# CH32V006K8U-R0.net
KiCad netlist of a schematic drawn in Altium Designer
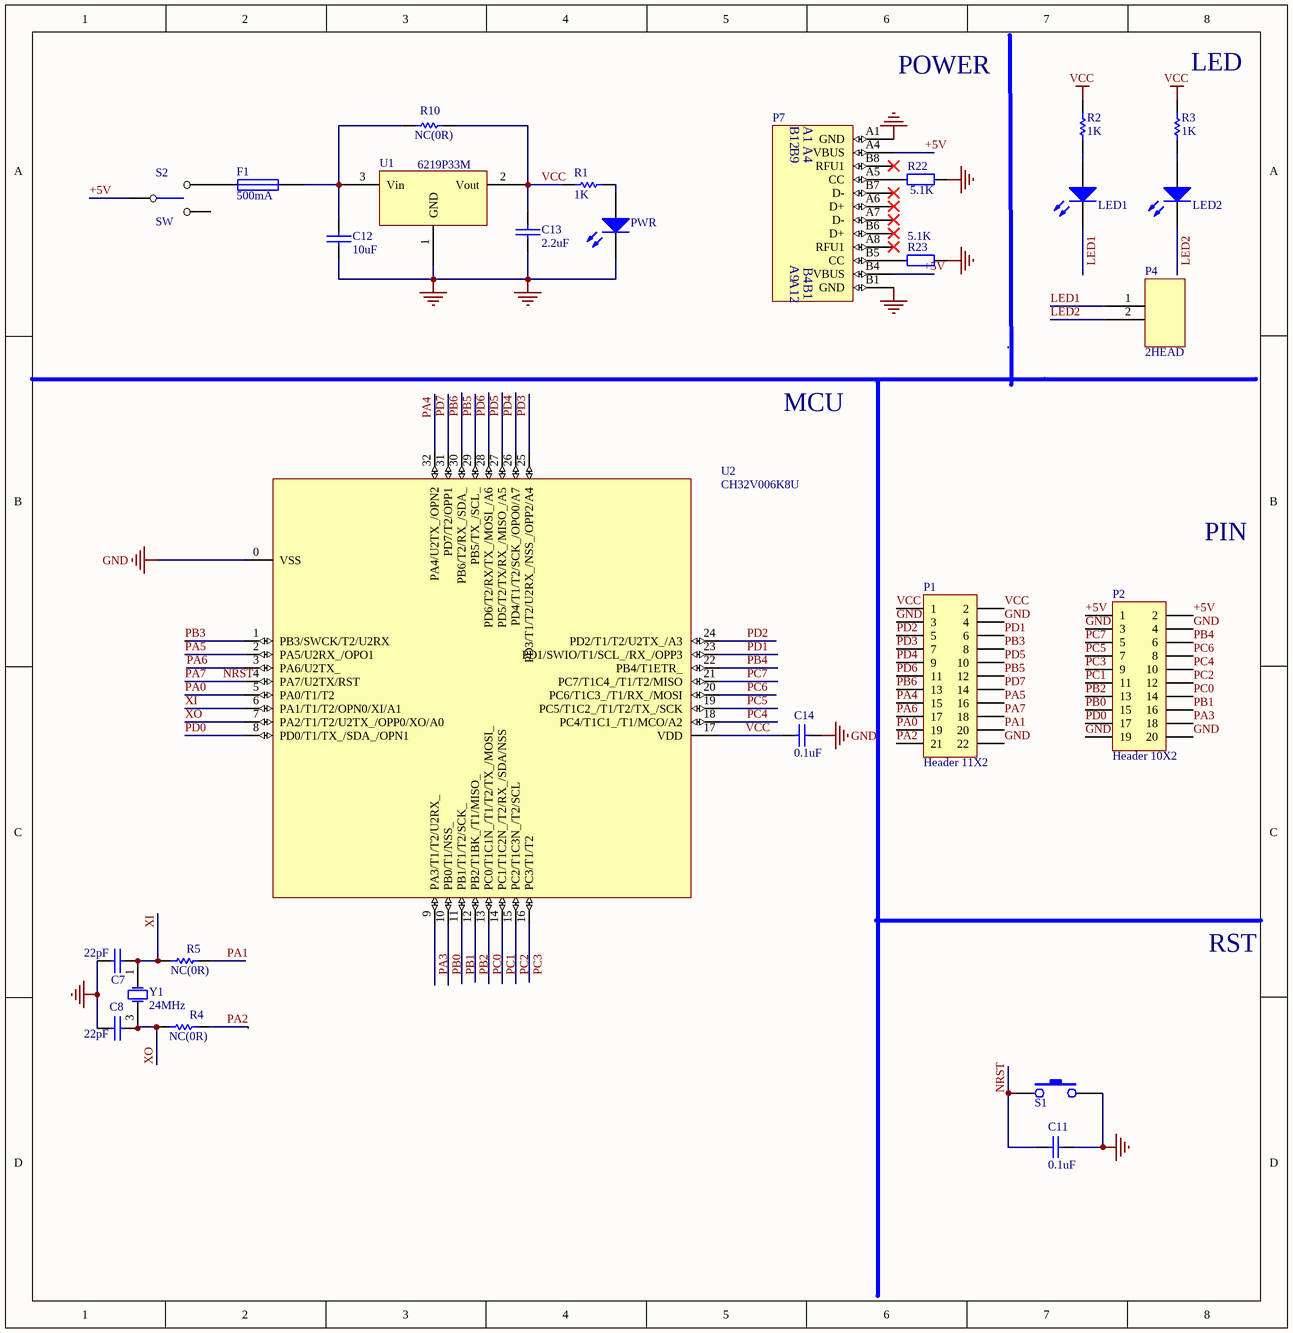
[diagram p0: CH32V006K8U-R0.SchDoc]

(export (version "E")
  (design (tool "Eeschema 10.0.6"))
  (components
    (comp (ref "C7")
      (value "22pF")
      (footprint "0402_C")
      (description "Capacitor")
      (libsource (lib "*") (part "CAP"))
    )
    (comp (ref "C8")
      (value "22pF")
      (footprint "0402_C")
      (description "Capacitor")
      (libsource (lib "*") (part "CAP"))
    )
    (comp (ref "C11")
      (value "0.1uF")
      (footprint "0402_C")
      (description "Capacitor")
      (fields (field (name "PUBLISHER") "Altium Limited"))
      (libsource (lib "*") (part "Cap"))
    )
    (comp (ref "C12")
      (value "10uF")
      (footprint "0603_C")
      (description "Capacitor")
      (libsource (lib "wch_sch_others") (part "CAP"))
    )
    (comp (ref "C13")
      (value "2.2uF")
      (footprint "0402_C")
      (description "Capacitor")
      (libsource (lib "wch_sch_others") (part "CAP"))
    )
    (comp (ref "C14")
      (value "0.1uF")
      (footprint "0402_C")
      (description "Capacitor")
      (fields (field (name "PUBLISHER") "Altium Limited"))
      (libsource (lib "*") (part "Cap"))
    )
    (comp (ref "F1")
      (value "500mA")
      (footprint "0603")
      (description "Fuse")
      (libsource (lib "*") (part "FUSE1"))
    )
    (comp (ref "LED1")
      (value "LED1   blue")
      (footprint "0603+")
      (description "Typical INFRARED GaAs LED")
      (fields (field (name "PUBLISHER") "Altium Limited"))
      (libsource (lib "*") (part "LED0"))
    )
    (comp (ref "LED2")
      (value "LED2  blue")
      (footprint "0603+")
      (description "Typical INFRARED GaAs LED")
      (fields (field (name "PUBLISHER") "Altium Limited"))
      (libsource (lib "*") (part "LED0"))
    )
    (comp (ref "P1")
      (value "Header 11X2")
      (footprint "IDC22-2.54mm")
      (description "Header, 11-Pin, Dual row")
      (fields (field (name "PUBLISHER") "Altium Limited"))
      (libsource (lib "Miscellaneous Connectors") (part "Header 11X2"))
    )
    (comp (ref "P2")
      (value "Header 10X2")
      (footprint "IDC20-2.54mm")
      (description "Header, 10-Pin, Dual row")
      (fields (field (name "PUBLISHER") "Altium Limited"))
      (libsource (lib "Miscellaneous Connectors") (part "Header 10X2"))
    )
    (comp (ref "P4") (value "2HEAD") (footprint "SIP2-2.54mm") (libsource (lib "*") (part "2HEAD")))
    (comp (ref "P7")
      (value "TYPE-C")
      (footprint "TYPE-C-Receptacle-2.0")
      (libsource (lib "*") (part "TYPE-C1"))
    )
    (comp (ref "PWR")
      (value "POWER  red")
      (footprint "0603+")
      (description "Typical INFRARED GaAs LED")
      (fields (field (name "PUBLISHER") "Altium Limited"))
      (libsource (lib "") (part "LED0_1"))
    )
    (comp (ref "R1")
      (value "1K")
      (footprint "0402")
      (description "Semiconductor Resistor")
      (fields (field (name "PUBLISHER") "Altium Limited"))
      (libsource (lib "*") (part "Res Semi"))
    )
    (comp (ref "R2")
      (value "1K")
      (footprint "0402")
      (description "Semiconductor Resistor")
      (fields (field (name "PUBLISHER") "Altium Limited"))
      (libsource (lib "*") (part "Res Semi"))
    )
    (comp (ref "R3")
      (value "1K")
      (footprint "0402")
      (description "Semiconductor Resistor")
      (fields (field (name "PUBLISHER") "Altium Limited"))
      (libsource (lib "*") (part "Res Semi"))
    )
    (comp (ref "R4")
      (value "NC(0R)")
      (footprint "0402")
      (description "Semiconductor Resistor")
      (fields (field (name "Comment") "0R") (field (name "PUBLISHER") "Altium Limited"))
      (libsource (lib "*") (part "Res Semi"))
    )
    (comp (ref "R5")
      (value "NC(0R)")
      (footprint "0402")
      (description "Semiconductor Resistor")
      (fields (field (name "Comment") "0R") (field (name "PUBLISHER") "Altium Limited"))
      (libsource (lib "*") (part "Res Semi"))
    )
    (comp (ref "R10")
      (value "NC(0R)")
      (footprint "0402")
      (description "Semiconductor Resistor")
      (fields (field (name "Comment") "0R") (field (name "PUBLISHER") "Altium Limited"))
      (libsource (lib "*") (part "Res Semi"))
    )
    (comp (ref "R22")
      (value "5.1K")
      (footprint "0402")
      (description "Resistor")
      (libsource (lib "Miscellaneous Devices") (part "Res2"))
    )
    (comp (ref "R23")
      (value "5.1K")
      (footprint "0402")
      (description "Resistor")
      (libsource (lib "Miscellaneous Devices") (part "Res2"))
    )
    (comp (ref "S1") (value "NRST") (footprint "SMD_6.1x3.65x2.5mm-KEY") (libsource (lib "*") (part "KEY")))
    (comp (ref "S2") (value "SW") (footprint "SW1") (libsource (lib "*") (part "SW")))
    (comp (ref "U1")
      (value "6219P33M")
      (footprint "SOT-23")
      (libsource (lib "wch_sch_others") (part "6219P33M"))
    )
    (comp (ref "U2")
      (value "CH32V006K8U")
      (footprint "QFN32_4X4")
      (description "RISC-V MCU, 48MHz, ADC/OPA/2*UART/I2C/SPI")
      (libsource (lib "PCB_Project") (part "CH32V006K8U"))
    )
    (comp (ref "Y1")
      (value "24MHz")
      (footprint "XT3225")
      (description "Crystal Oscillator")
      (fields (field (name "PUBLISHER") "Altium Limited"))
      (libsource (lib "*") (part "XTAL"))
    )
  )
  (nets
    (net (code "1") (name "/+5V") (class "Default")
      (node (ref "P2") (pin "1") (pinfunction "1_1") (pintype "passive"))
      (node (ref "P2") (pin "2") (pinfunction "2_2") (pintype "passive"))
      (node (ref "P7") (pin "A4") (pinfunction "VBUS_A4") (pintype "bidirectional"))
      (node (ref "P7") (pin "B4") (pinfunction "VBUS_B4") (pintype "bidirectional"))
      (node (ref "S2") (pin "1") (pinfunction "1_1") (pintype "passive"))
    )
    (net (code "2") (name "/LED1") (class "Default")
      (node (ref "LED1") (pin "2") (pinfunction "K_2") (pintype "passive"))
      (node (ref "P4") (pin "1") (pintype "passive"))
    )
    (net (code "3") (name "/LED2") (class "Default")
      (node (ref "LED2") (pin "2") (pinfunction "K_2") (pintype "passive"))
      (node (ref "P4") (pin "2") (pintype "passive"))
    )
    (net (code "4") (name "/NRST") (class "Default")
      (node (ref "C11") (pin "2") (pinfunction "2_2") (pintype "passive"))
      (node (ref "P1") (pin "18") (pinfunction "18_18") (pintype "passive"))
      (node (ref "S1") (pin "1") (pinfunction "1_1") (pintype "passive"))
      (node (ref "U2") (pin "4") (pinfunction "PA7/U2TX/RST_4") (pintype "bidirectional"))
    )
    (net (code "5") (name "/PA0") (class "Default")
      (node (ref "P1") (pin "19") (pinfunction "19_19") (pintype "passive"))
      (node (ref "U2") (pin "5") (pinfunction "PA0/T1/T2_5") (pintype "bidirectional"))
    )
    (net (code "6") (name "/PA1") (class "Default")
      (node (ref "P1") (pin "20") (pinfunction "20_20") (pintype "passive"))
      (node (ref "R5") (pin "2") (pinfunction "2_2") (pintype "passive"))
    )
    (net (code "7") (name "/PA2") (class "Default")
      (node (ref "P1") (pin "21") (pinfunction "21_21") (pintype "passive"))
      (node (ref "R4") (pin "2") (pinfunction "2_2") (pintype "passive"))
    )
    (net (code "8") (name "/PA3") (class "Default")
      (node (ref "P2") (pin "18") (pinfunction "18_18") (pintype "passive"))
      (node (ref "U2") (pin "9") (pinfunction "PA3/T1/T2/U2RX__9") (pintype "bidirectional"))
    )
    (net (code "9") (name "/PA4") (class "Default")
      (node (ref "P1") (pin "15") (pinfunction "15_15") (pintype "passive"))
      (node (ref "U2") (pin "32") (pinfunction "PA4/U2TX_/OPN2_32") (pintype "bidirectional"))
    )
    (net (code "10") (name "/PA5") (class "Default")
      (node (ref "P1") (pin "16") (pinfunction "16_16") (pintype "passive"))
      (node (ref "U2") (pin "2") (pinfunction "PA5/U2RX_/OPO1_2") (pintype "bidirectional"))
    )
    (net (code "11") (name "/PA6") (class "Default")
      (node (ref "P1") (pin "17") (pinfunction "17_17") (pintype "passive"))
      (node (ref "U2") (pin "3") (pinfunction "PA6/U2TX__3") (pintype "bidirectional"))
    )
    (net (code "12") (name "/PB0") (class "Default")
      (node (ref "P2") (pin "15") (pinfunction "15_15") (pintype "passive"))
      (node (ref "U2") (pin "10") (pinfunction "PB0/T1/NSS__10") (pintype "bidirectional"))
    )
    (net (code "13") (name "/PB1") (class "Default")
      (node (ref "P2") (pin "16") (pinfunction "16_16") (pintype "passive"))
      (node (ref "U2") (pin "11") (pinfunction "PB1/T1/T2/SCK__11") (pintype "bidirectional"))
    )
    (net (code "14") (name "/PB2") (class "Default")
      (node (ref "P2") (pin "13") (pinfunction "13_13") (pintype "passive"))
      (node (ref "U2") (pin "12") (pinfunction "PB2/T1BK_/T1/MISO__12") (pintype "bidirectional"))
    )
    (net (code "15") (name "/PB3") (class "Default")
      (node (ref "P1") (pin "8") (pinfunction "8_8") (pintype "passive"))
      (node (ref "U2") (pin "1") (pinfunction "PB3/SWCK/T2/U2RX_1") (pintype "bidirectional"))
    )
    (net (code "16") (name "/PB4") (class "Default")
      (node (ref "P2") (pin "6") (pinfunction "6_6") (pintype "passive"))
      (node (ref "U2") (pin "22") (pinfunction "PB4/T1ETR__22") (pintype "bidirectional"))
    )
    (net (code "17") (name "/PB5") (class "Default")
      (node (ref "P1") (pin "12") (pinfunction "12_12") (pintype "passive"))
      (node (ref "U2") (pin "29") (pinfunction "PB5/TX_/SCL__29") (pintype "bidirectional"))
    )
    (net (code "18") (name "/PB6") (class "Default")
      (node (ref "P1") (pin "13") (pinfunction "13_13") (pintype "passive"))
      (node (ref "U2") (pin "30") (pinfunction "PB6/T2/RX_/SDA__30") (pintype "bidirectional"))
    )
    (net (code "19") (name "/PC0") (class "Default")
      (node (ref "P2") (pin "14") (pinfunction "14_14") (pintype "passive"))
      (node (ref "U2") (pin "13") (pinfunction "PC0/T1C1N_/T1/T2/TX_/MOSI__13") (pintype "bidirectional"))
    )
    (net (code "20") (name "/PC1") (class "Default")
      (node (ref "P2") (pin "11") (pinfunction "11_11") (pintype "passive"))
      (node (ref "U2") (pin "14") (pinfunction "PC1/T1C2N_/T2/RX_/SDA/NSS_14") (pintype "bidirectional"))
    )
    (net (code "21") (name "/PC2") (class "Default")
      (node (ref "P2") (pin "12") (pinfunction "12_12") (pintype "passive"))
      (node (ref "U2") (pin "15") (pinfunction "PC2/T1C3N_/T2/SCL_15") (pintype "bidirectional"))
    )
    (net (code "22") (name "/PC3") (class "Default")
      (node (ref "P2") (pin "9") (pinfunction "9_9") (pintype "passive"))
      (node (ref "U2") (pin "16") (pinfunction "PC3/T1/T2_16") (pintype "bidirectional"))
    )
    (net (code "23") (name "/PC4") (class "Default")
      (node (ref "P2") (pin "10") (pinfunction "10_10") (pintype "passive"))
      (node (ref "U2") (pin "18") (pinfunction "PC4/T1C1_/T1/MCO/A2_18") (pintype "bidirectional"))
    )
    (net (code "24") (name "/PC5") (class "Default")
      (node (ref "P2") (pin "7") (pinfunction "7_7") (pintype "passive"))
      (node (ref "U2") (pin "19") (pinfunction "PC5/T1C2_/T1/T2/TX_/SCK_19") (pintype "bidirectional"))
    )
    (net (code "25") (name "/PC6") (class "Default")
      (node (ref "P2") (pin "8") (pinfunction "8_8") (pintype "passive"))
      (node (ref "U2") (pin "20") (pinfunction "PC6/T1C3_/T1/RX_/MOSI_20") (pintype "bidirectional"))
    )
    (net (code "26") (name "/PC7") (class "Default")
      (node (ref "P2") (pin "5") (pinfunction "5_5") (pintype "passive"))
      (node (ref "U2") (pin "21") (pinfunction "PC7/T1C4_/T1/T2/MISO_21") (pintype "bidirectional"))
    )
    (net (code "27") (name "/PD0") (class "Default")
      (node (ref "P2") (pin "17") (pinfunction "17_17") (pintype "passive"))
      (node (ref "U2") (pin "8") (pinfunction "PD0/T1/TX_/SDA_/OPN1_8") (pintype "bidirectional"))
    )
    (net (code "28") (name "/PD1") (class "Default")
      (node (ref "P1") (pin "6") (pinfunction "6_6") (pintype "passive"))
      (node (ref "U2") (pin "23") (pinfunction "PD1/SWIO/T1/SCL_/RX_/OPP3_23") (pintype "bidirectional"))
    )
    (net (code "29") (name "/PD2") (class "Default")
      (node (ref "P1") (pin "5") (pinfunction "5_5") (pintype "passive"))
      (node (ref "U2") (pin "24") (pinfunction "PD2/T1/T2/U2TX_/A3_24") (pintype "bidirectional"))
    )
    (net (code "30") (name "/PD3") (class "Default")
      (node (ref "P1") (pin "7") (pinfunction "7_7") (pintype "passive"))
      (node (ref "U2") (pin "25") (pinfunction "PD3/T1/T2/U2RX_/NSS_/OPP2/A4_25") (pintype "bidirectional"))
    )
    (net (code "31") (name "/PD4") (class "Default")
      (node (ref "P1") (pin "9") (pinfunction "9_9") (pintype "passive"))
      (node (ref "U2") (pin "26") (pinfunction "PD4/T1/T2/SCK_/OPO0/A7_26") (pintype "bidirectional"))
    )
    (net (code "32") (name "/PD5") (class "Default")
      (node (ref "P1") (pin "10") (pinfunction "10_10") (pintype "passive"))
      (node (ref "U2") (pin "27") (pinfunction "PD5/T2/TX/RX_/MISO_/A5_27") (pintype "bidirectional"))
    )
    (net (code "33") (name "/PD6") (class "Default")
      (node (ref "P1") (pin "11") (pinfunction "11_11") (pintype "passive"))
      (node (ref "U2") (pin "28") (pinfunction "PD6/T2/RX/TX_/MOSI_/A6_28") (pintype "bidirectional"))
    )
    (net (code "34") (name "/PD7") (class "Default")
      (node (ref "P1") (pin "14") (pinfunction "14_14") (pintype "passive"))
      (node (ref "U2") (pin "31") (pinfunction "PD7/T2/OPP1_31") (pintype "bidirectional"))
    )
    (net (code "35") (name "/XI") (class "Default")
      (node (ref "C7") (pin "2") (pinfunction "2_2") (pintype "passive"))
      (node (ref "R5") (pin "1") (pinfunction "1_1") (pintype "passive"))
      (node (ref "U2") (pin "6") (pinfunction "PA1/T1/T2/OPN0/XI/A1_6") (pintype "bidirectional"))
      (node (ref "Y1") (pin "1") (pinfunction "OSC1_1") (pintype "passive"))
    )
    (net (code "36") (name "/XO") (class "Default")
      (node (ref "C8") (pin "2") (pinfunction "2_2") (pintype "passive"))
      (node (ref "R4") (pin "1") (pinfunction "1_1") (pintype "passive"))
      (node (ref "U2") (pin "7") (pinfunction "PA2/T1/T2/U2TX_/OPP0/XO/A0_7") (pintype "bidirectional"))
      (node (ref "Y1") (pin "3") (pinfunction "OSC2_3") (pintype "passive"))
    )
    (net (code "37") (name "GND") (class "Default")
      (node (ref "C11") (pin "1") (pinfunction "1_1") (pintype "passive"))
      (node (ref "C12") (pin "2") (pinfunction "2_2") (pintype "passive"))
      (node (ref "C13") (pin "1") (pinfunction "1_1") (pintype "passive"))
      (node (ref "C14") (pin "2") (pinfunction "2_2") (pintype "passive"))
      (node (ref "C7") (pin "1") (pinfunction "1_1") (pintype "passive"))
      (node (ref "C8") (pin "1") (pinfunction "1_1") (pintype "passive"))
      (node (ref "P1") (pin "22") (pinfunction "22_22") (pintype "passive"))
      (node (ref "P1") (pin "3") (pinfunction "3_3") (pintype "passive"))
      (node (ref "P1") (pin "4") (pinfunction "4_4") (pintype "passive"))
      (node (ref "P2") (pin "19") (pinfunction "19_19") (pintype "passive"))
      (node (ref "P2") (pin "20") (pinfunction "20_20") (pintype "passive"))
      (node (ref "P2") (pin "3") (pinfunction "3_3") (pintype "passive"))
      (node (ref "P2") (pin "4") (pinfunction "4_4") (pintype "passive"))
      (node (ref "P7") (pin "A1") (pinfunction "GND_A1") (pintype "bidirectional"))
      (node (ref "P7") (pin "B1") (pinfunction "GND_B1") (pintype "bidirectional"))
      (node (ref "PWR") (pin "2") (pinfunction "K_2") (pintype "passive"))
      (node (ref "R22") (pin "2") (pinfunction "2_2") (pintype "passive"))
      (node (ref "R23") (pin "2") (pinfunction "2_2") (pintype "passive"))
      (node (ref "S1") (pin "2") (pinfunction "2_2") (pintype "passive"))
      (node (ref "U1") (pin "1") (pinfunction "GND_1") (pintype "passive"))
      (node (ref "U2") (pin "0") (pinfunction "VSS_0") (pintype "power_in"))
    )
    (net (code "38") (name "Net-(F1-Pad1)") (class "Default")
      (node (ref "F1") (pin "1") (pinfunction "1_1") (pintype "passive"))
      (node (ref "S2") (pin "3") (pinfunction "3_3") (pintype "passive"))
    )
    (net (code "39") (name "Net-(LED1-A)") (class "Default")
      (node (ref "LED1") (pin "1") (pinfunction "A_1") (pintype "passive"))
      (node (ref "R2") (pin "2") (pinfunction "2_2") (pintype "passive"))
    )
    (net (code "40") (name "Net-(LED2-A)") (class "Default")
      (node (ref "LED2") (pin "1") (pinfunction "A_1") (pintype "passive"))
      (node (ref "R3") (pin "2") (pinfunction "2_2") (pintype "passive"))
    )
    (net (code "41") (name "Net-(P7-CC-PadA5)") (class "Default")
      (node (ref "P7") (pin "A5") (pinfunction "CC_A5") (pintype "bidirectional"))
      (node (ref "R22") (pin "1") (pinfunction "1_1") (pintype "passive"))
    )
    (net (code "42") (name "Net-(P7-CC-PadB5)") (class "Default")
      (node (ref "P7") (pin "B5") (pinfunction "CC_B5") (pintype "bidirectional"))
      (node (ref "R23") (pin "1") (pinfunction "1_1") (pintype "passive"))
    )
    (net (code "43") (name "Net-(PWR-A)") (class "Default")
      (node (ref "PWR") (pin "1") (pinfunction "A_1") (pintype "passive"))
      (node (ref "R1") (pin "1") (pinfunction "1_1") (pintype "passive"))
    )
    (net (code "44") (name "Net-(U1-Vin)") (class "Default")
      (node (ref "C12") (pin "1") (pinfunction "1_1") (pintype "passive"))
      (node (ref "F1") (pin "2") (pinfunction "2_2") (pintype "passive"))
      (node (ref "R10") (pin "1") (pinfunction "1_1") (pintype "passive"))
      (node (ref "U1") (pin "3") (pinfunction "Vin_3") (pintype "passive"))
    )
    (net (code "45") (name "VCC") (class "Default")
      (node (ref "C13") (pin "2") (pinfunction "2_2") (pintype "passive"))
      (node (ref "C14") (pin "1") (pinfunction "1_1") (pintype "passive"))
      (node (ref "P1") (pin "1") (pinfunction "1_1") (pintype "passive"))
      (node (ref "P1") (pin "2") (pinfunction "2_2") (pintype "passive"))
      (node (ref "R1") (pin "2") (pinfunction "2_2") (pintype "passive"))
      (node (ref "R10") (pin "2") (pinfunction "2_2") (pintype "passive"))
      (node (ref "R2") (pin "1") (pinfunction "1_1") (pintype "passive"))
      (node (ref "R3") (pin "1") (pinfunction "1_1") (pintype "passive"))
      (node (ref "U1") (pin "2") (pinfunction "Vout_2") (pintype "passive"))
      (node (ref "U2") (pin "17") (pinfunction "VDD_17") (pintype "power_in"))
    )
    (net (code "46") (name "unconnected-(P7-D+-PadA6)") (class "Default")
      (node (ref "P7") (pin "A6") (pinfunction "D+_A6") (pintype "bidirectional+no_connect"))
    )
    (net (code "47") (name "unconnected-(P7-D+-PadB6)") (class "Default")
      (node (ref "P7") (pin "B6") (pinfunction "D+_B6") (pintype "bidirectional+no_connect"))
    )
    (net (code "48") (name "unconnected-(P7-D--PadA7)") (class "Default")
      (node (ref "P7") (pin "A7") (pinfunction "D-_A7") (pintype "bidirectional+no_connect"))
    )
    (net (code "49") (name "unconnected-(P7-D--PadB7)") (class "Default")
      (node (ref "P7") (pin "B7") (pinfunction "D-_B7") (pintype "bidirectional+no_connect"))
    )
    (net (code "50") (name "unconnected-(P7-RFU1-PadA8)") (class "Default")
      (node (ref "P7") (pin "A8") (pinfunction "RFU1_A8") (pintype "bidirectional+no_connect"))
    )
    (net (code "51") (name "unconnected-(P7-RFU1-PadB8)") (class "Default")
      (node (ref "P7") (pin "B8") (pinfunction "RFU1_B8") (pintype "bidirectional+no_connect"))
    )
    (net (code "52") (name "unconnected-(S2-Pad2)") (class "Default")
      (node (ref "S2") (pin "2") (pinfunction "2_2") (pintype "passive"))
    )
  )
)
